# 32x35_V0_3.net
KiCad netlist of a schematic drawn in Altium Designer
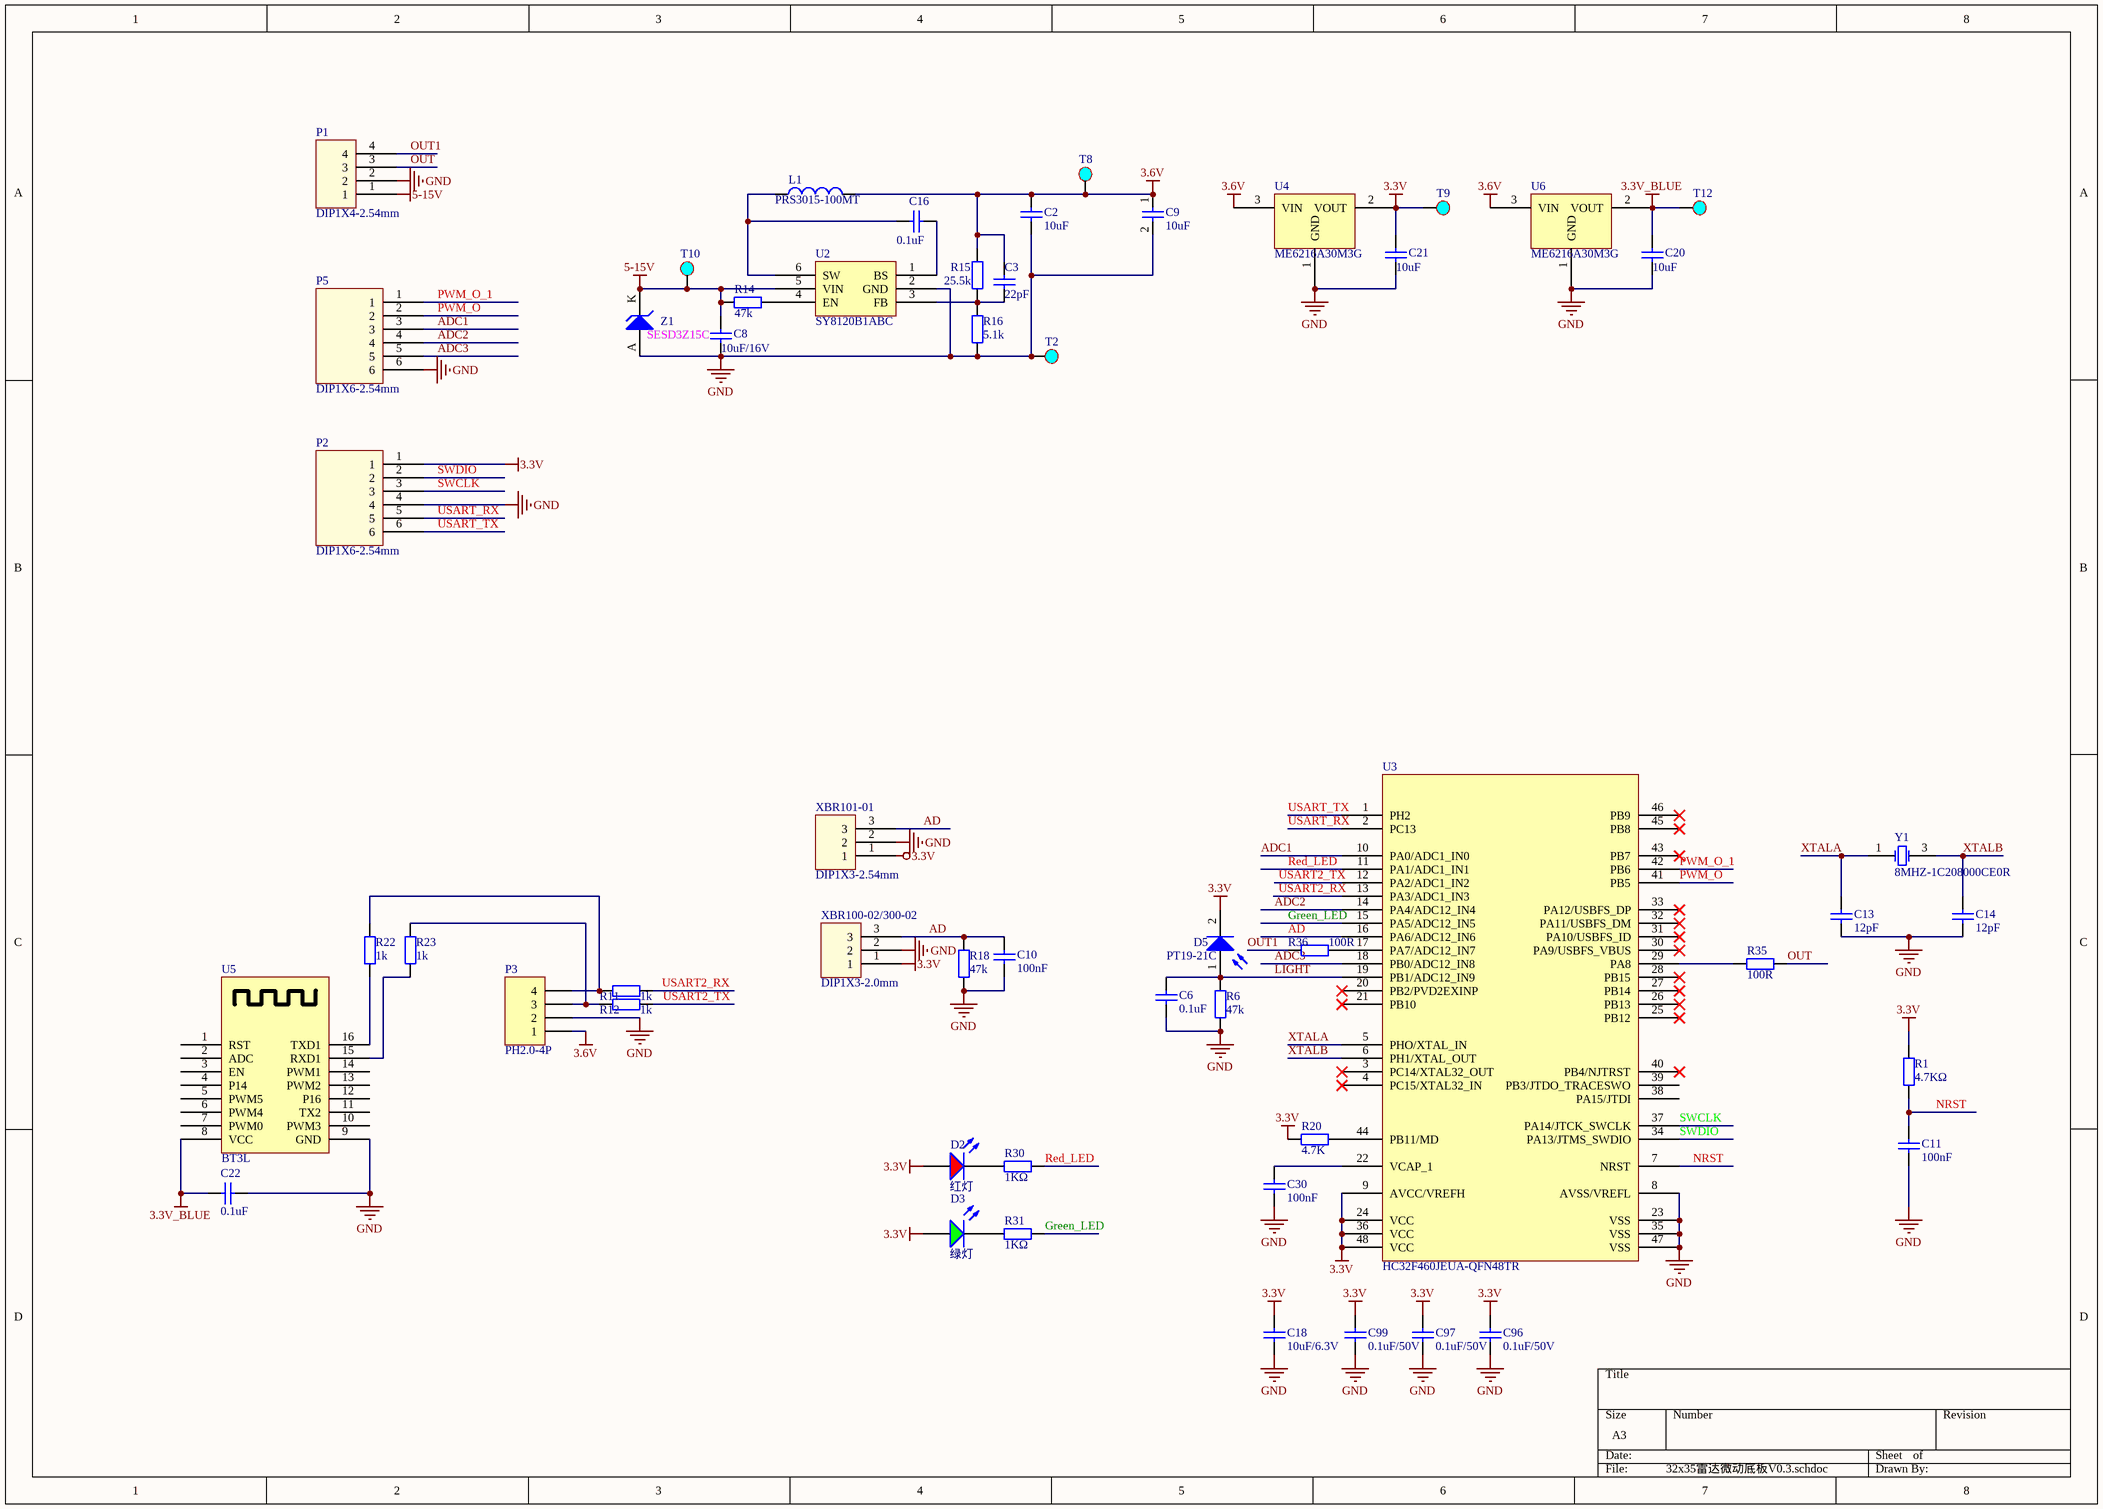
[diagram p0: 32x35雷达微动底板V0.3.schdoc]

(export (version "E")
  (design (tool "Eeschema 10.0.6"))
  (components
    (comp (ref "C2")
      (value "10uF")
      (footprint "C0402")
      (description "Capacitor")
      (fields (field (name "PUBLISHER") "Altium Limited"))
      (libsource (lib "Miscellaneous Devices") (part "Cap"))
    )
    (comp (ref "C3")
      (value "22pF")
      (footprint "C0402")
      (description "Capacitor")
      (fields (field (name "PUBLISHER") "Altium Limited"))
      (libsource (lib "Miscellaneous Devices") (part "Cap"))
    )
    (comp (ref "C6")
      (value "0.1uF")
      (footprint "C0402")
      (description "Capacitor")
      (fields (field (name "PUBLISHER") "Altium Limited"))
      (libsource (lib "Miscellaneous Devices") (part "Cap"))
    )
    (comp (ref "C8")
      (value "10uF/16V")
      (footprint "C0603")
      (description "Capacitor")
      (fields (field (name "PUBLISHER") "Altium Limited"))
      (libsource (lib "Miscellaneous Devices") (part "Cap"))
    )
    (comp (ref "C9")
      (value "10uF")
      (footprint "C0402")
      (description "Capacitor")
      (fields (field (name "PUBLISHER") "Altium Limited"))
      (libsource (lib "") (part "Cap_1"))
    )
    (comp (ref "C10")
      (value "100nF")
      (footprint "C0402")
      (description "Capacitor")
      (fields (field (name "PUBLISHER") "Altium Limited"))
      (libsource (lib "Miscellaneous Devices") (part "Cap"))
    )
    (comp (ref "C11")
      (value "100nF")
      (footprint "C0402")
      (description "贴片电容")
      (libsource (lib "Miscellaneous Devices LC") (part "0402 100nF (104) 10% 16V"))
    )
    (comp (ref "C13")
      (value "12pF")
      (footprint "C0402")
      (description "贴片电容")
      (libsource (lib "Cap") (part "0402 22pF (220) 5% 50V"))
    )
    (comp (ref "C14")
      (value "12pF")
      (footprint "C0402")
      (description "贴片电容")
      (libsource (lib "Cap") (part "0402 22pF (220) 5% 50V"))
    )
    (comp (ref "C16")
      (value "0.1uF")
      (footprint "C0402")
      (description "Capacitor")
      (fields (field (name "PUBLISHER") "Altium Limited"))
      (libsource (lib "Miscellaneous Devices") (part "Cap"))
    )
    (comp (ref "C18")
      (value "10uF/6.3V")
      (footprint "C0402")
      (description "贴片电容")
      (libsource (lib "Cap") (part "0402 2.2nF (222) 10% 50V"))
    )
    (comp (ref "C20")
      (value "10uF")
      (footprint "C0402")
      (description "Capacitor")
      (fields (field (name "PUBLISHER") "Altium Limited"))
      (libsource (lib "Miscellaneous Devices") (part "Cap"))
    )
    (comp (ref "C21")
      (value "10uF")
      (footprint "C0402")
      (description "Capacitor")
      (fields (field (name "PUBLISHER") "Altium Limited"))
      (libsource (lib "Miscellaneous Devices") (part "Cap"))
    )
    (comp (ref "C22")
      (value "0.1uF")
      (footprint "C0402")
      (description "Capacitor")
      (fields (field (name "PUBLISHER") "Altium Limited"))
      (libsource (lib "Miscellaneous Devices") (part "Cap"))
    )
    (comp (ref "C30")
      (value "100nF")
      (footprint "C0402")
      (description "Capacitor")
      (fields (field (name "PUBLISHER") "Altium Limited"))
      (libsource (lib "Miscellaneous Devices") (part "Cap"))
    )
    (comp (ref "C96")
      (value "0.1uF/50V")
      (footprint "C0402")
      (description "贴片电容")
      (libsource (lib "Cap") (part "0402 2.2nF (222) 10% 50V"))
    )
    (comp (ref "C97")
      (value "0.1uF/50V")
      (footprint "C0402")
      (description "贴片电容")
      (libsource (lib "Cap") (part "0402 2.2nF (222) 10% 50V"))
    )
    (comp (ref "C99")
      (value "0.1uF/50V")
      (footprint "C0402")
      (description "贴片电容")
      (libsource (lib "Cap") (part "0402 2.2nF (222) 10% 50V"))
    )
    (comp (ref "D2")
      (value "红灯")
      (footprint "LC-0603_LED_S1")
      (description "发光二极管")
      (libsource (lib "Miscellaneous Devices LC") (part "0603 红灯"))
    )
    (comp (ref "D3")
      (value "绿灯")
      (footprint "LC-0603_LED_S1")
      (description "发光二极管")
      (libsource (lib "30x35雷达微动底板V0.2") (part "0603 红灯"))
    )
    (comp (ref "D5")
      (value "PT19-21C")
      (footprint "LED-0603")
      (description "Photosensitive Diode")
      (fields (field (name "PUBLISHER") "Altium Limited"))
      (libsource (lib "Miscellaneous Devices") (part "Photo Sen"))
    )
    (comp (ref "L1")
      (value "PRS3015-100MT")
      (footprint "PRS3015")
      (description "Inductor")
      (fields (field (name "PUBLISHER") "Altium Limited"))
      (libsource (lib "Miscellaneous Devices") (part "Inductor"))
    )
    (comp (ref "P1")
      (value "DIP1X4-2.54mm")
      (footprint "DIP1X4-2.54mm")
      (libsource (lib "30x35雷达微动底板V0.2") (part "DIP4-2.54mm"))
    )
    (comp (ref "P2")
      (value "DIP1X6-2.54mm")
      (footprint "DIP1X6-2.54")
      (libsource (lib "30x35雷达微动底板V0.2") (part "DIP1X6-2.54mm"))
    )
    (comp (ref "P3")
      (value "PH2.0-4P")
      (footprint "PH2.0-5P")
      (description "Header, 4-Pin")
      (fields (field (name "PUBLISHER") "Altium Limited"))
      (libsource (lib "*") (part "Header 4"))
    )
    (comp (ref "P5")
      (value "DIP1X6-2.54mm")
      (footprint "DIP1X6-2.54")
      (libsource (lib "30x35雷达微动底板V0.2") (part "DIP1X6-2.54mm"))
    )
    (comp (ref "R1")
      (value "4.7KΩ")
      (footprint "R0402")
      (description "贴片电阻")
      (libsource (lib "") (part "0402 4.7KΩ (4701) 1%_1"))
    )
    (comp (ref "R6")
      (value "47k")
      (footprint "R0402")
      (description "Resistor")
      (fields (field (name "PUBLISHER") "Altium Limited"))
      (libsource (lib "Miscellaneous Devices") (part "Res2"))
    )
    (comp (ref "R11")
      (value "1k")
      (footprint "R0402")
      (description "Resistor")
      (fields (field (name "PUBLISHER") "Altium Limited"))
      (libsource (lib "") (part "Res2_1"))
    )
    (comp (ref "R12")
      (value "1k")
      (footprint "R0402")
      (description "Resistor")
      (fields (field (name "PUBLISHER") "Altium Limited"))
      (libsource (lib "") (part "Res2_1"))
    )
    (comp (ref "R14")
      (value "47k")
      (footprint "R0402")
      (description "Resistor")
      (fields (field (name "PUBLISHER") "Altium Limited"))
      (libsource (lib "") (part "Res2_1"))
    )
    (comp (ref "R15")
      (value "25.5k")
      (footprint "R0402")
      (description "Resistor")
      (fields (field (name "PUBLISHER") "Altium Limited"))
      (libsource (lib "") (part "Res2_2"))
    )
    (comp (ref "R16")
      (value "5.1k")
      (footprint "R0402")
      (description "Resistor")
      (fields (field (name "PUBLISHER") "Altium Limited"))
      (libsource (lib "") (part "Res2_2"))
    )
    (comp (ref "R18")
      (value "47k")
      (footprint "R0402")
      (description "Resistor")
      (fields (field (name "PUBLISHER") "Altium Limited"))
      (libsource (lib "Miscellaneous Devices") (part "Res2"))
    )
    (comp (ref "R20")
      (value "4.7K")
      (footprint "R0402")
      (description "Resistor")
      (fields (field (name "PUBLISHER") "Altium Limited"))
      (libsource (lib "") (part "Res2_3"))
    )
    (comp (ref "R22")
      (value "1k")
      (footprint "R0402")
      (description "Resistor")
      (fields (field (name "PUBLISHER") "Altium Limited"))
      (libsource (lib "Miscellaneous Devices") (part "Res2"))
    )
    (comp (ref "R23")
      (value "1k")
      (footprint "R0402")
      (description "Resistor")
      (fields (field (name "PUBLISHER") "Altium Limited"))
      (libsource (lib "Miscellaneous Devices") (part "Res2"))
    )
    (comp (ref "R30")
      (value "1KΩ")
      (footprint "R0402")
      (description "贴片电阻")
      (libsource (lib "Miscellaneous Devices LC") (part "0402 1KΩ (1001) 1%"))
    )
    (comp (ref "R31")
      (value "1KΩ")
      (footprint "R0402")
      (description "贴片电阻")
      (libsource (lib "Miscellaneous Devices LC") (part "0402 1KΩ (1001) 1%"))
    )
    (comp (ref "R35")
      (value "100R")
      (footprint "R0402")
      (description "贴片电阻")
      (libsource (lib "Miscellaneous Devices LC") (part "0402 4.7KΩ (4701) 1%"))
    )
    (comp (ref "R36")
      (value "100R")
      (footprint "R0402")
      (description "贴片电阻")
      (libsource (lib "Miscellaneous Devices LC") (part "0402 4.7KΩ (4701) 1%"))
    )
    (comp (ref "T2")
      (value "~")
      (footprint "TestPoints")
      (description "TestPoints")
      (libsource (lib "标准原理图库（特种板）") (part "TestPoints"))
    )
    (comp (ref "T8")
      (value "~")
      (footprint "TestPoints")
      (description "TestPoints")
      (libsource (lib "标准原理图库（特种板）") (part "TestPoints"))
    )
    (comp (ref "T9")
      (value "~")
      (footprint "TestPoints")
      (description "TestPoints")
      (libsource (lib "标准原理图库（特种板）") (part "TestPoints"))
    )
    (comp (ref "T10")
      (value "~")
      (footprint "TestPoints")
      (description "TestPoints")
      (libsource (lib "标准原理图库（特种板）") (part "TestPoints"))
    )
    (comp (ref "T12")
      (value "~")
      (footprint "TestPoints")
      (description "TestPoints")
      (libsource (lib "标准原理图库（特种板）") (part "TestPoints"))
    )
    (comp (ref "U2") (value "SY8120B1ABC") (footprint "SOT-23-6") (libsource (lib "Schlib1") (part "H9108")))
    (comp (ref "U3")
      (value "HC32F460JEUA-QFN48TR")
      (footprint "QFN48-5X5mm")
      (libsource (lib "LD-ShouShi-Module-V1.0") (part "HC32F460JETA-LQFP48"))
    )
    (comp (ref "U4")
      (value "ME6216A30M3G")
      (footprint "SOT-23-L")
      (libsource (lib "Schlib1") (part "SSP6206"))
    )
    (comp (ref "U5") (value "BT3L") (footprint "ZS3L") (libsource (lib "Schlib-BLE") (part "BT3L")))
    (comp (ref "U6")
      (value "ME6216A30M3G")
      (footprint "SOT-23-L")
      (libsource (lib "Schlib1") (part "SSP6206"))
    )
    (comp (ref "XBR100-02/300-02")
      (value "DIP1X3-2.0mm")
      (footprint "XBR100-02")
      (libsource (lib "12IO") (part "DIP1X3-2.54mm"))
    )
    (comp (ref "XBR101-01")
      (value "DIP1X3-2.54mm")
      (footprint "XBR101-01")
      (libsource (lib "12IO") (part "DIP1X3-2.54mm"))
    )
    (comp (ref "Y1")
      (value "8MHZ-1C208000CE0R")
      (footprint "OSC-SMD_3225")
      (description "贴片晶振")
      (libsource (lib "CrystalOscillator") (part "SMD-3225_4P  25MHZ 12PF 10PPM"))
    )
    (comp (ref "Z1")
      (value "SESD3Z15C")
      (footprint "SOD323")
      (description "Zener Diode")
      (fields (field (name "PUBLISHER") "Altium Limited"))
      (libsource (lib "Miscellaneous Devices") (part "D Zener"))
    )
  )
  (nets
    (net (code "1") (name "/AD") (class "Default")
      (node (ref "C10") (pin "1") (pinfunction "1_1") (pintype "passive"))
      (node (ref "R18") (pin "1") (pinfunction "1_1") (pintype "passive"))
      (node (ref "U3") (pin "16") (pinfunction "PA6/ADC12_IN6_16") (pintype "passive"))
      (node (ref "XBR100-02/300-02") (pin "3") (pinfunction "3_3") (pintype "passive"))
      (node (ref "XBR101-01") (pin "3") (pinfunction "3_3") (pintype "passive"))
    )
    (net (code "2") (name "/ADC1") (class "Default")
      (node (ref "P5") (pin "3") (pinfunction "3_3") (pintype "passive"))
      (node (ref "U3") (pin "10") (pinfunction "PA0/ADC1_IN0_10") (pintype "passive"))
    )
    (net (code "3") (name "/ADC2") (class "Default")
      (node (ref "P5") (pin "4") (pinfunction "4_4") (pintype "passive"))
      (node (ref "U3") (pin "14") (pinfunction "PA4/ADC12_IN4_14") (pintype "passive"))
    )
    (net (code "4") (name "/ADC3") (class "Default")
      (node (ref "P5") (pin "5") (pinfunction "5_5") (pintype "passive"))
      (node (ref "U3") (pin "18") (pinfunction "PB0/ADC12_IN8_18") (pintype "passive"))
    )
    (net (code "5") (name "/Green_LED") (class "Default")
      (node (ref "R31") (pin "1") (pinfunction "1_1") (pintype "passive"))
      (node (ref "U3") (pin "15") (pinfunction "PA5/ADC12_IN5_15") (pintype "passive"))
    )
    (net (code "6") (name "/LIGHT") (class "Default")
      (node (ref "C6") (pin "1") (pinfunction "1_1") (pintype "passive"))
      (node (ref "D5") (pin "1") (pinfunction "A_1") (pintype "passive"))
      (node (ref "R6") (pin "1") (pinfunction "1_1") (pintype "passive"))
      (node (ref "U3") (pin "19") (pinfunction "PB1/ADC12_IN9_19") (pintype "passive"))
    )
    (net (code "7") (name "/NRST") (class "Default")
      (node (ref "C11") (pin "2") (pinfunction "2_2") (pintype "passive"))
      (node (ref "R1") (pin "1") (pinfunction "1_1") (pintype "passive"))
      (node (ref "U3") (pin "7") (pinfunction "NRST_7") (pintype "passive"))
    )
    (net (code "8") (name "/OUT") (class "Default")
      (node (ref "P1") (pin "3") (pinfunction "3_3") (pintype "passive"))
      (node (ref "R35") (pin "1") (pinfunction "1_1") (pintype "passive"))
    )
    (net (code "9") (name "/OUT1") (class "Default")
      (node (ref "P1") (pin "4") (pinfunction "4_4") (pintype "passive"))
      (node (ref "R36") (pin "2") (pinfunction "2_2") (pintype "passive"))
    )
    (net (code "10") (name "/PWM_O") (class "Default")
      (node (ref "P5") (pin "2") (pinfunction "2_2") (pintype "passive"))
      (node (ref "U3") (pin "41") (pinfunction "PB5_41") (pintype "passive"))
    )
    (net (code "11") (name "/PWM_O_1") (class "Default")
      (node (ref "P5") (pin "1") (pinfunction "1_1") (pintype "passive"))
      (node (ref "U3") (pin "42") (pinfunction "PB6_42") (pintype "passive"))
    )
    (net (code "12") (name "/Red_LED") (class "Default")
      (node (ref "R30") (pin "1") (pinfunction "1_1") (pintype "passive"))
      (node (ref "U3") (pin "11") (pinfunction "PA1/ADC1_IN1_11") (pintype "passive"))
    )
    (net (code "13") (name "/SWCLK") (class "Default")
      (node (ref "P2") (pin "3") (pinfunction "3_3") (pintype "passive"))
      (node (ref "U3") (pin "37") (pinfunction "PA14/JTCK_SWCLK_37") (pintype "passive"))
    )
    (net (code "14") (name "/SWDIO") (class "Default")
      (node (ref "P2") (pin "2") (pinfunction "2_2") (pintype "passive"))
      (node (ref "U3") (pin "34") (pinfunction "PA13/JTMS_SWDIO_34") (pintype "passive"))
    )
    (net (code "15") (name "/USART2_RX") (class "Default")
      (node (ref "R11") (pin "1") (pinfunction "1_1") (pintype "passive"))
      (node (ref "U3") (pin "13") (pinfunction "PA3/ADC1_IN3_13") (pintype "passive"))
    )
    (net (code "16") (name "/USART2_TX") (class "Default")
      (node (ref "R12") (pin "1") (pinfunction "1_1") (pintype "passive"))
      (node (ref "U3") (pin "12") (pinfunction "PA2/ADC1_IN2_12") (pintype "passive"))
    )
    (net (code "17") (name "/USART_RX") (class "Default")
      (node (ref "P2") (pin "5") (pinfunction "5_5") (pintype "passive"))
      (node (ref "U3") (pin "2") (pinfunction "PC13_2") (pintype "passive"))
    )
    (net (code "18") (name "/USART_TX") (class "Default")
      (node (ref "P2") (pin "6") (pinfunction "6_6") (pintype "passive"))
      (node (ref "U3") (pin "1") (pinfunction "PH2_1") (pintype "passive"))
    )
    (net (code "19") (name "/XTALA") (class "Default")
      (node (ref "C13") (pin "2") (pinfunction "2_2") (pintype "passive"))
      (node (ref "U3") (pin "5") (pinfunction "PHO/XTAL_IN_5") (pintype "passive"))
      (node (ref "Y1") (pin "1") (pinfunction "OSC1_1") (pintype "passive"))
    )
    (net (code "20") (name "/XTALB") (class "Default")
      (node (ref "C14") (pin "2") (pinfunction "2_2") (pintype "passive"))
      (node (ref "U3") (pin "6") (pinfunction "PH1/XTAL_OUT_6") (pintype "passive"))
      (node (ref "Y1") (pin "3") (pinfunction "OSC2_3") (pintype "passive"))
    )
    (net (code "21") (name "3.3V") (class "Default")
      (node (ref "C18") (pin "1") (pinfunction "1_1") (pintype "passive"))
      (node (ref "C21") (pin "1") (pinfunction "1_1") (pintype "passive"))
      (node (ref "C96") (pin "1") (pinfunction "1_1") (pintype "passive"))
      (node (ref "C97") (pin "1") (pinfunction "1_1") (pintype "passive"))
      (node (ref "C99") (pin "1") (pinfunction "1_1") (pintype "passive"))
      (node (ref "D2") (pin "A") (pinfunction "A_A") (pintype "passive"))
      (node (ref "D3") (pin "A") (pinfunction "A_A") (pintype "passive"))
      (node (ref "D5") (pin "2") (pinfunction "K_2") (pintype "passive"))
      (node (ref "P2") (pin "1") (pinfunction "1_1") (pintype "passive"))
      (node (ref "R1") (pin "2") (pinfunction "2_2") (pintype "passive"))
      (node (ref "R20") (pin "1") (pinfunction "1_1") (pintype "passive"))
      (node (ref "T9") (pin "1") (pinfunction "1_1") (pintype "passive"))
      (node (ref "U3") (pin "24") (pinfunction "VCC_24") (pintype "passive"))
      (node (ref "U3") (pin "36") (pinfunction "VCC_36") (pintype "passive"))
      (node (ref "U3") (pin "48") (pinfunction "VCC_48") (pintype "passive"))
      (node (ref "U3") (pin "9") (pinfunction "AVCC/VREFH_9") (pintype "passive"))
      (node (ref "U4") (pin "2") (pinfunction "VOUT_2") (pintype "passive"))
      (node (ref "XBR100-02/300-02") (pin "1") (pinfunction "1_1") (pintype "passive"))
      (node (ref "XBR101-01") (pin "1") (pinfunction "1_1") (pintype "passive"))
    )
    (net (code "22") (name "3.3V_BLUE") (class "Default")
      (node (ref "C20") (pin "1") (pinfunction "1_1") (pintype "passive"))
      (node (ref "C22") (pin "1") (pinfunction "1_1") (pintype "passive"))
      (node (ref "T12") (pin "1") (pinfunction "1_1") (pintype "passive"))
      (node (ref "U5") (pin "8") (pinfunction "VCC_8") (pintype "passive"))
      (node (ref "U6") (pin "2") (pinfunction "VOUT_2") (pintype "passive"))
    )
    (net (code "23") (name "3.6V") (class "Default")
      (node (ref "C2") (pin "1") (pinfunction "1_1") (pintype "passive"))
      (node (ref "C3") (pin "2") (pinfunction "2_2") (pintype "passive"))
      (node (ref "C9") (pin "1") (pinfunction "1_1") (pintype "passive"))
      (node (ref "L1") (pin "2") (pinfunction "2_2") (pintype "passive"))
      (node (ref "P3") (pin "1") (pinfunction "1_1") (pintype "passive"))
      (node (ref "R15") (pin "2") (pinfunction "2_2") (pintype "passive"))
      (node (ref "T8") (pin "1") (pinfunction "1_1") (pintype "passive"))
      (node (ref "U4") (pin "3") (pinfunction "VIN_3") (pintype "passive"))
      (node (ref "U6") (pin "3") (pinfunction "VIN_3") (pintype "passive"))
    )
    (net (code "24") (name "5-15V") (class "Default")
      (node (ref "C8") (pin "1") (pinfunction "1_1") (pintype "passive"))
      (node (ref "P1") (pin "1") (pinfunction "1_1") (pintype "passive"))
      (node (ref "R14") (pin "2") (pinfunction "2_2") (pintype "passive"))
      (node (ref "T10") (pin "1") (pinfunction "1_1") (pintype "passive"))
      (node (ref "U2") (pin "5") (pinfunction "VIN_5") (pintype "passive"))
      (node (ref "Z1") (pin "K") (pinfunction "K_K") (pintype "passive"))
    )
    (net (code "25") (name "GND") (class "Default")
      (node (ref "C10") (pin "2") (pinfunction "2_2") (pintype "passive"))
      (node (ref "C11") (pin "1") (pinfunction "1_1") (pintype "passive"))
      (node (ref "C13") (pin "1") (pinfunction "1_1") (pintype "passive"))
      (node (ref "C14") (pin "1") (pinfunction "1_1") (pintype "passive"))
      (node (ref "C18") (pin "2") (pinfunction "2_2") (pintype "passive"))
      (node (ref "C2") (pin "2") (pinfunction "2_2") (pintype "passive"))
      (node (ref "C20") (pin "2") (pinfunction "2_2") (pintype "passive"))
      (node (ref "C21") (pin "2") (pinfunction "2_2") (pintype "passive"))
      (node (ref "C22") (pin "2") (pinfunction "2_2") (pintype "passive"))
      (node (ref "C30") (pin "2") (pinfunction "2_2") (pintype "passive"))
      (node (ref "C6") (pin "2") (pinfunction "2_2") (pintype "passive"))
      (node (ref "C8") (pin "2") (pinfunction "2_2") (pintype "passive"))
      (node (ref "C9") (pin "2") (pinfunction "2_2") (pintype "passive"))
      (node (ref "C96") (pin "2") (pinfunction "2_2") (pintype "passive"))
      (node (ref "C97") (pin "2") (pinfunction "2_2") (pintype "passive"))
      (node (ref "C99") (pin "2") (pinfunction "2_2") (pintype "passive"))
      (node (ref "P1") (pin "2") (pinfunction "2_2") (pintype "passive"))
      (node (ref "P2") (pin "4") (pinfunction "4_4") (pintype "passive"))
      (node (ref "P3") (pin "2") (pinfunction "2_2") (pintype "passive"))
      (node (ref "P5") (pin "6") (pinfunction "6_6") (pintype "passive"))
      (node (ref "R16") (pin "1") (pinfunction "1_1") (pintype "passive"))
      (node (ref "R18") (pin "2") (pinfunction "2_2") (pintype "passive"))
      (node (ref "R6") (pin "2") (pinfunction "2_2") (pintype "passive"))
      (node (ref "T2") (pin "1") (pinfunction "1_1") (pintype "passive"))
      (node (ref "U2") (pin "2") (pinfunction "GND_2") (pintype "passive"))
      (node (ref "U3") (pin "23") (pinfunction "VSS_23") (pintype "passive"))
      (node (ref "U3") (pin "35") (pinfunction "VSS_35") (pintype "passive"))
      (node (ref "U3") (pin "47") (pinfunction "VSS_47") (pintype "passive"))
      (node (ref "U3") (pin "8") (pinfunction "AVSS/VREFL_8") (pintype "passive"))
      (node (ref "U4") (pin "1") (pinfunction "GND_1") (pintype "passive"))
      (node (ref "U5") (pin "9") (pinfunction "GND_9") (pintype "passive"))
      (node (ref "U6") (pin "1") (pinfunction "GND_1") (pintype "passive"))
      (node (ref "XBR100-02/300-02") (pin "2") (pinfunction "2_2") (pintype "passive"))
      (node (ref "XBR101-01") (pin "2") (pinfunction "2_2") (pintype "passive"))
      (node (ref "Z1") (pin "A") (pinfunction "A_A") (pintype "passive"))
    )
    (net (code "26") (name "Net-(D2-PadK)") (class "Default")
      (node (ref "D2") (pin "K") (pinfunction "K_K") (pintype "passive"))
      (node (ref "R30") (pin "2") (pinfunction "2_2") (pintype "passive"))
    )
    (net (code "27") (name "Net-(D3-PadK)") (class "Default")
      (node (ref "D3") (pin "K") (pinfunction "K_K") (pintype "passive"))
      (node (ref "R31") (pin "2") (pinfunction "2_2") (pintype "passive"))
    )
    (net (code "28") (name "Net-(P3-Pad3)") (class "Default")
      (node (ref "P3") (pin "3") (pinfunction "3_3") (pintype "passive"))
      (node (ref "R12") (pin "2") (pinfunction "2_2") (pintype "passive"))
      (node (ref "R23") (pin "1") (pinfunction "1_1") (pintype "passive"))
    )
    (net (code "29") (name "Net-(P3-Pad4)") (class "Default")
      (node (ref "P3") (pin "4") (pinfunction "4_4") (pintype "passive"))
      (node (ref "R11") (pin "2") (pinfunction "2_2") (pintype "passive"))
      (node (ref "R22") (pin "1") (pinfunction "1_1") (pintype "passive"))
    )
    (net (code "30") (name "Net-(U2-BS)") (class "Default")
      (node (ref "C16") (pin "2") (pinfunction "2_2") (pintype "passive"))
      (node (ref "U2") (pin "1") (pinfunction "BS_1") (pintype "passive"))
    )
    (net (code "31") (name "Net-(U2-EN)") (class "Default")
      (node (ref "R14") (pin "1") (pinfunction "1_1") (pintype "passive"))
      (node (ref "U2") (pin "4") (pinfunction "EN_4") (pintype "passive"))
    )
    (net (code "32") (name "Net-(U2-FB)") (class "Default")
      (node (ref "C3") (pin "1") (pinfunction "1_1") (pintype "passive"))
      (node (ref "R15") (pin "1") (pinfunction "1_1") (pintype "passive"))
      (node (ref "R16") (pin "2") (pinfunction "2_2") (pintype "passive"))
      (node (ref "U2") (pin "3") (pinfunction "FB_3") (pintype "passive"))
    )
    (net (code "33") (name "Net-(U2-SW)") (class "Default")
      (node (ref "C16") (pin "1") (pinfunction "1_1") (pintype "passive"))
      (node (ref "L1") (pin "1") (pinfunction "1_1") (pintype "passive"))
      (node (ref "U2") (pin "6") (pinfunction "SW_6") (pintype "passive"))
    )
    (net (code "34") (name "Net-(U3-PA7{slash}ADC12_IN7)") (class "Default")
      (node (ref "R36") (pin "1") (pinfunction "1_1") (pintype "passive"))
      (node (ref "U3") (pin "17") (pinfunction "PA7/ADC12_IN7_17") (pintype "passive"))
    )
    (net (code "35") (name "Net-(U3-PA8)") (class "Default")
      (node (ref "R35") (pin "2") (pinfunction "2_2") (pintype "passive"))
      (node (ref "U3") (pin "29") (pinfunction "PA8_29") (pintype "passive"))
    )
    (net (code "36") (name "Net-(U3-PB11{slash}MD)") (class "Default")
      (node (ref "R20") (pin "2") (pinfunction "2_2") (pintype "passive"))
      (node (ref "U3") (pin "44") (pinfunction "PB11/MD_44") (pintype "passive"))
    )
    (net (code "37") (name "Net-(U3-VCAP_1)") (class "Default")
      (node (ref "C30") (pin "1") (pinfunction "1_1") (pintype "passive"))
      (node (ref "U3") (pin "22") (pinfunction "VCAP_1_22") (pintype "passive"))
    )
    (net (code "38") (name "Net-(U5-RXD1)") (class "Default")
      (node (ref "R23") (pin "2") (pinfunction "2_2") (pintype "passive"))
      (node (ref "U5") (pin "15") (pinfunction "RXD1_15") (pintype "passive"))
    )
    (net (code "39") (name "Net-(U5-TXD1)") (class "Default")
      (node (ref "R22") (pin "2") (pinfunction "2_2") (pintype "passive"))
      (node (ref "U5") (pin "16") (pinfunction "TXD1_16") (pintype "passive"))
    )
    (net (code "40") (name "unconnected-(U3-PA9{slash}USBFS_VBUS-Pad30)") (class "Default")
      (node (ref "U3") (pin "30") (pinfunction "PA9/USBFS_VBUS_30") (pintype "passive+no_connect"))
    )
    (net (code "41") (name "unconnected-(U3-PA10{slash}USBFS_ID-Pad31)") (class "Default")
      (node (ref "U3") (pin "31") (pinfunction "PA10/USBFS_ID_31") (pintype "passive+no_connect"))
    )
    (net (code "42") (name "unconnected-(U3-PA11{slash}USBFS_DM-Pad32)") (class "Default")
      (node (ref "U3") (pin "32") (pinfunction "PA11/USBFS_DM_32") (pintype "passive+no_connect"))
    )
    (net (code "43") (name "unconnected-(U3-PA12{slash}USBFS_DP-Pad33)") (class "Default")
      (node (ref "U3") (pin "33") (pinfunction "PA12/USBFS_DP_33") (pintype "passive+no_connect"))
    )
    (net (code "44") (name "unconnected-(U3-PA15{slash}JTDI-Pad38)") (class "Default")
      (node (ref "U3") (pin "38") (pinfunction "PA15/JTDI_38") (pintype "passive"))
    )
    (net (code "45") (name "unconnected-(U3-PB2{slash}PVD2EXINP-Pad20)") (class "Default")
      (node (ref "U3") (pin "20") (pinfunction "PB2/PVD2EXINP_20") (pintype "passive+no_connect"))
    )
    (net (code "46") (name "unconnected-(U3-PB3{slash}JTDO_TRACESWO-Pad39)") (class "Default")
      (node (ref "U3") (pin "39") (pinfunction "PB3/JTDO_TRACESWO_39") (pintype "passive"))
    )
    (net (code "47") (name "unconnected-(U3-PB4{slash}NJTRST-Pad40)") (class "Default")
      (node (ref "U3") (pin "40") (pinfunction "PB4/NJTRST_40") (pintype "passive+no_connect"))
    )
    (net (code "48") (name "unconnected-(U3-PB7-Pad43)") (class "Default")
      (node (ref "U3") (pin "43") (pinfunction "PB7_43") (pintype "passive+no_connect"))
    )
    (net (code "49") (name "unconnected-(U3-PB8-Pad45)") (class "Default")
      (node (ref "U3") (pin "45") (pinfunction "PB8_45") (pintype "passive+no_connect"))
    )
    (net (code "50") (name "unconnected-(U3-PB9-Pad46)") (class "Default")
      (node (ref "U3") (pin "46") (pinfunction "PB9_46") (pintype "passive+no_connect"))
    )
    (net (code "51") (name "unconnected-(U3-PB10-Pad21)") (class "Default")
      (node (ref "U3") (pin "21") (pinfunction "PB10_21") (pintype "passive+no_connect"))
    )
    (net (code "52") (name "unconnected-(U3-PB12-Pad25)") (class "Default")
      (node (ref "U3") (pin "25") (pinfunction "PB12_25") (pintype "passive+no_connect"))
    )
    (net (code "53") (name "unconnected-(U3-PB13-Pad26)") (class "Default")
      (node (ref "U3") (pin "26") (pinfunction "PB13_26") (pintype "passive+no_connect"))
    )
    (net (code "54") (name "unconnected-(U3-PB14-Pad27)") (class "Default")
      (node (ref "U3") (pin "27") (pinfunction "PB14_27") (pintype "passive+no_connect"))
    )
    (net (code "55") (name "unconnected-(U3-PB15-Pad28)") (class "Default")
      (node (ref "U3") (pin "28") (pinfunction "PB15_28") (pintype "passive+no_connect"))
    )
    (net (code "56") (name "unconnected-(U3-PC14{slash}XTAL32_OUT-Pad3)") (class "Default")
      (node (ref "U3") (pin "3") (pinfunction "PC14/XTAL32_OUT_3") (pintype "passive+no_connect"))
    )
    (net (code "57") (name "unconnected-(U3-PC15{slash}XTAL32_IN-Pad4)") (class "Default")
      (node (ref "U3") (pin "4") (pinfunction "PC15/XTAL32_IN_4") (pintype "passive+no_connect"))
    )
    (net (code "58") (name "unconnected-(U5-ADC-Pad2)") (class "Default")
      (node (ref "U5") (pin "2") (pinfunction "ADC_2") (pintype "passive"))
    )
    (net (code "59") (name "unconnected-(U5-EN-Pad3)") (class "Default")
      (node (ref "U5") (pin "3") (pinfunction "EN_3") (pintype "passive"))
    )
    (net (code "60") (name "unconnected-(U5-P14-Pad4)") (class "Default")
      (node (ref "U5") (pin "4") (pinfunction "P14_4") (pintype "passive"))
    )
    (net (code "61") (name "unconnected-(U5-P16-Pad12)") (class "Default")
      (node (ref "U5") (pin "12") (pinfunction "P16_12") (pintype "passive"))
    )
    (net (code "62") (name "unconnected-(U5-PWM0-Pad7)") (class "Default")
      (node (ref "U5") (pin "7") (pinfunction "PWM0_7") (pintype "passive"))
    )
    (net (code "63") (name "unconnected-(U5-PWM1-Pad14)") (class "Default")
      (node (ref "U5") (pin "14") (pinfunction "PWM1_14") (pintype "passive"))
    )
    (net (code "64") (name "unconnected-(U5-PWM2-Pad13)") (class "Default")
      (node (ref "U5") (pin "13") (pinfunction "PWM2_13") (pintype "passive"))
    )
    (net (code "65") (name "unconnected-(U5-PWM3-Pad10)") (class "Default")
      (node (ref "U5") (pin "10") (pinfunction "PWM3_10") (pintype "passive"))
    )
    (net (code "66") (name "unconnected-(U5-PWM4-Pad6)") (class "Default")
      (node (ref "U5") (pin "6") (pinfunction "PWM4_6") (pintype "passive"))
    )
    (net (code "67") (name "unconnected-(U5-PWM5-Pad5)") (class "Default")
      (node (ref "U5") (pin "5") (pinfunction "PWM5_5") (pintype "passive"))
    )
    (net (code "68") (name "unconnected-(U5-RST-Pad1)") (class "Default")
      (node (ref "U5") (pin "1") (pinfunction "RST_1") (pintype "passive"))
    )
    (net (code "69") (name "unconnected-(U5-TX2-Pad11)") (class "Default")
      (node (ref "U5") (pin "11") (pinfunction "TX2_11") (pintype "passive"))
    )
  )
)
